# P01_PMIC.net
KiCad netlist of a schematic drawn in Altium Designer
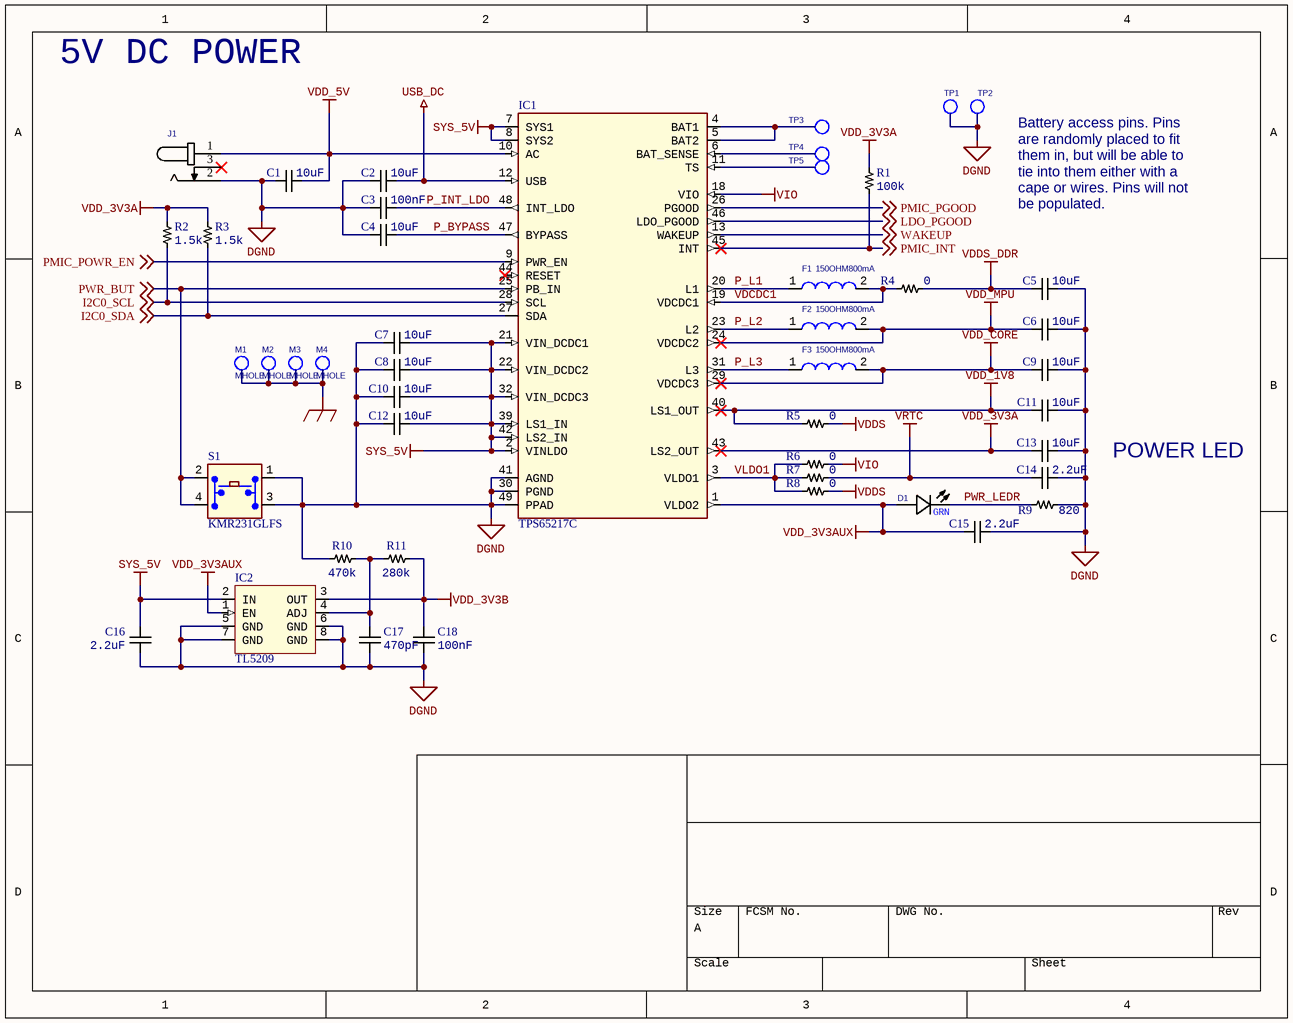
[diagram p0: P01_PMIC.SchDoc]

(export (version "E")
  (design (tool "Eeschema 10.0.6"))
  (components
    (comp (ref "C1")
      (value "C2012X6S1A106K085AC")
      (footprint "Orient:CAP0805")
      (description "MLCC 10uF 0805 SMD")
      (fields
        (field (name "MANUFACTURER") "TDK")
        (field (name "TOLERANCE") "10%")
        (field (name "CAPACITANCE") "10uF")
      )
      (libsource (lib "Orient") (part "CAP_10uF"))
    )
    (comp (ref "C2")
      (value "C2012X6S1A106K085AC")
      (footprint "Orient:CAP0805")
      (description "MLCC 10uF 0805 SMD")
      (fields
        (field (name "MANUFACTURER") "TDK")
        (field (name "TOLERANCE") "10%")
        (field (name "CAPACITANCE") "10uF")
      )
      (libsource (lib "Orient") (part "CAP_10uF"))
    )
    (comp (ref "C3")
      (value "C0402C104K4RACTU")
      (footprint "Orient:CAP0402")
      (description "MLCC 100nF 0402 SMD")
      (fields
        (field (name "MANUFACTURER") "KEMET")
        (field (name "TOLERANCE") "10%")
        (field (name "CAPACITANCE") "100nF")
      )
      (libsource (lib "Orient") (part "CAP_100nF"))
    )
    (comp (ref "C4")
      (value "C2012X6S1A106K085AC")
      (footprint "Orient:CAP0805")
      (description "MLCC 10uF 0805 SMD")
      (fields
        (field (name "MANUFACTURER") "TDK")
        (field (name "TOLERANCE") "10%")
        (field (name "CAPACITANCE") "10uF")
      )
      (libsource (lib "Orient") (part "CAP_10uF"))
    )
    (comp (ref "C5")
      (value "C2012X6S1A106K085AC")
      (footprint "Orient:CAP0805")
      (description "MLCC 10uF 0805 SMD")
      (fields
        (field (name "MANUFACTURER") "TDK")
        (field (name "TOLERANCE") "10%")
        (field (name "CAPACITANCE") "10uF")
      )
      (libsource (lib "Orient") (part "CAP_10uF"))
    )
    (comp (ref "C6")
      (value "C2012X6S1A106K085AC")
      (footprint "Orient:CAP0805")
      (description "MLCC 10uF 0805 SMD")
      (fields
        (field (name "MANUFACTURER") "TDK")
        (field (name "TOLERANCE") "10%")
        (field (name "CAPACITANCE") "10uF")
      )
      (libsource (lib "Orient") (part "CAP_10uF"))
    )
    (comp (ref "C7")
      (value "C2012X6S1A106K085AC")
      (footprint "Orient:CAP0805")
      (description "MLCC 10uF 0805 SMD")
      (fields
        (field (name "MANUFACTURER") "TDK")
        (field (name "TOLERANCE") "10%")
        (field (name "CAPACITANCE") "10uF")
      )
      (libsource (lib "Orient") (part "CAP_10uF"))
    )
    (comp (ref "C8")
      (value "C2012X6S1A106K085AC")
      (footprint "Orient:CAP0805")
      (description "MLCC 10uF 0805 SMD")
      (fields
        (field (name "MANUFACTURER") "TDK")
        (field (name "TOLERANCE") "10%")
        (field (name "CAPACITANCE") "10uF")
      )
      (libsource (lib "Orient") (part "CAP_10uF"))
    )
    (comp (ref "C9")
      (value "C2012X6S1A106K085AC")
      (footprint "Orient:CAP0805")
      (description "MLCC 10uF 0805 SMD")
      (fields
        (field (name "MANUFACTURER") "TDK")
        (field (name "TOLERANCE") "10%")
        (field (name "CAPACITANCE") "10uF")
      )
      (libsource (lib "Orient") (part "CAP_10uF"))
    )
    (comp (ref "C10")
      (value "C2012X6S1A106K085AC")
      (footprint "Orient:CAP0805")
      (description "MLCC 10uF 0805 SMD")
      (fields
        (field (name "MANUFACTURER") "TDK")
        (field (name "TOLERANCE") "10%")
        (field (name "CAPACITANCE") "10uF")
      )
      (libsource (lib "Orient") (part "CAP_10uF"))
    )
    (comp (ref "C11")
      (value "C2012X6S1A106K085AC")
      (footprint "Orient:CAP0805")
      (description "MLCC 10uF 0805 SMD")
      (fields
        (field (name "MANUFACTURER") "TDK")
        (field (name "TOLERANCE") "10%")
        (field (name "CAPACITANCE") "10uF")
      )
      (libsource (lib "Orient") (part "CAP_10uF"))
    )
    (comp (ref "C12")
      (value "C2012X6S1A106K085AC")
      (footprint "Orient:CAP0805")
      (description "MLCC 10uF 0805 SMD")
      (fields
        (field (name "MANUFACTURER") "TDK")
        (field (name "TOLERANCE") "10%")
        (field (name "CAPACITANCE") "10uF")
      )
      (libsource (lib "Orient") (part "CAP_10uF"))
    )
    (comp (ref "C13")
      (value "C2012X6S1A106K085AC")
      (footprint "Orient:CAP0805")
      (description "MLCC 10uF 0805 SMD")
      (fields
        (field (name "MANUFACTURER") "TDK")
        (field (name "TOLERANCE") "10%")
        (field (name "CAPACITANCE") "10uF")
      )
      (libsource (lib "Orient") (part "CAP_10uF"))
    )
    (comp (ref "C14")
      (value "C1005X5R0J225K050BC")
      (footprint "Orient:CAP0402")
      (description "MLCC 2.2uF 0402 SMD")
      (fields
        (field (name "MANUFACTURER") "TDK")
        (field (name "TOLERANCE") "10%")
        (field (name "CAPACITANCE") "2.2uF")
      )
      (libsource (lib "Orient") (part "CAP_2.2uF"))
    )
    (comp (ref "C15")
      (value "C1005X5R0J225K050BC")
      (footprint "Orient:CAP0402")
      (description "MLCC 2.2uF 0402 SMD")
      (fields
        (field (name "MANUFACTURER") "TDK")
        (field (name "TOLERANCE") "10%")
        (field (name "CAPACITANCE") "2.2uF")
      )
      (libsource (lib "Orient") (part "CAP_2.2uF"))
    )
    (comp (ref "C16")
      (value "C1005X5R0J225K050BC")
      (footprint "Orient:CAP0402")
      (description "MLCC 2.2uF 0402 SMD")
      (fields
        (field (name "MANUFACTURER") "TDK")
        (field (name "TOLERANCE") "10%")
        (field (name "CAPACITANCE") "2.2uF")
      )
      (libsource (lib "Orient") (part "CAP_2.2uF"))
    )
    (comp (ref "C17")
      (value "GRM155R71H471KA01D")
      (footprint "Orient:CAP0402")
      (description "MLCC 470pF 0402 SMD")
      (fields
        (field (name "MANUFACTURER") "Murata")
        (field (name "TOLERANCE") "10%")
        (field (name "CAPACITANCE") "470pF")
      )
      (libsource (lib "Orient") (part "CAP_470pF"))
    )
    (comp (ref "C18")
      (value "C0402C104K4RACTU")
      (footprint "Orient:CAP0402")
      (description "MLCC 100nF 0402 SMD")
      (fields
        (field (name "MANUFACTURER") "KEMET")
        (field (name "TOLERANCE") "10%")
        (field (name "CAPACITANCE") "100nF")
      )
      (libsource (lib "Orient") (part "CAP_100nF"))
    )
    (comp (ref "D1")
      (value "598-8170-107F")
      (footprint "Orient:LED_0603")
      (description "LED GREEN CLEAR 0805 SMD")
      (fields
        (field (name "MANUFACTURER") "Lite-On Inc")
        (field (name "MANUFACTURER PART NUMBER") "LTST-C170KGKT")
      )
      (libsource (lib "Orient") (part "LED_LTST-C150GKT"))
    )
    (comp (ref "F1")
      (value "150OHM800mA")
      (footprint "Orient:FB0805")
      (description "FERRITE 800MA 150 OHM 0805 SMD")
      (fields
        (field (name "MANUFACTURER") "Laird-Signal Integrity Products")
        (field (name "MANUFACTURER PART NUMBER") "LI0805H151R-10")
      )
      (libsource (lib "Orient") (part "IND"))
    )
    (comp (ref "F2")
      (value "150OHM800mA")
      (footprint "Orient:FB0805")
      (description "FERRITE 800MA 150 OHM 0805 SMD")
      (fields
        (field (name "MANUFACTURER") "Laird-Signal Integrity Products")
        (field (name "MANUFACTURER PART NUMBER") "LI0805H151R-10")
      )
      (libsource (lib "Orient") (part "IND"))
    )
    (comp (ref "F3")
      (value "150OHM800mA")
      (footprint "Orient:FB0805")
      (description "FERRITE 800MA 150 OHM 0805 SMD")
      (fields
        (field (name "MANUFACTURER") "Laird-Signal Integrity Products")
        (field (name "MANUFACTURER PART NUMBER") "LI0805H151R-10")
      )
      (libsource (lib "Orient") (part "IND"))
    )
    (comp (ref "IC1")
      (value "TPS65217C")
      (footprint "Orient:PVQFN-48")
      (description "IC PMIC BATT PWR SYST 48VQFN")
      (fields
        (field (name "MANUFACTURER") "Texas Instruments")
        (field (name "MANUFACTURER PART NUMBER") "TPS65217CRSLR")
      )
      (libsource (lib "Orient") (part "TPS65217C"))
    )
    (comp (ref "IC2")
      (value "TL5209")
      (footprint "Orient:SOIC-8")
      (description "LDO Voltage Regulator")
      (fields
        (field (name "MANUFACTURER") "Texas Instruments")
        (field (name "MANUFACTURER PART NUMBER") "TL5209DR")
      )
      (libsource (lib "Orient") (part "TL5209"))
    )
    (comp (ref "J1")
      (value "PJ-200A")
      (description "CONN PWR JACK 2.1X5.5MM HIGH CUR")
      (fields (field (name "MANUFACTURER") "CUI Inc") (field (name "MANUFACTURER PART NUMBER") "PJ-002AH"))
      (libsource (lib "Orient") (part "Power_Jack"))
    )
    (comp (ref "M1")
      (value "MHOLE")
      (footprint "Orient:MTGH200C125D_PL")
      (libsource (lib "Orient") (part "MHOLE"))
    )
    (comp (ref "M2")
      (value "MHOLE")
      (footprint "Orient:MTGH200C125D_PL")
      (libsource (lib "Orient") (part "MHOLE"))
    )
    (comp (ref "M3")
      (value "MHOLE")
      (footprint "Orient:MTGH200C125D_PL")
      (libsource (lib "Orient") (part "MHOLE"))
    )
    (comp (ref "M4")
      (value "MHOLE")
      (footprint "Orient:MTGH200C125D_PL")
      (libsource (lib "Orient") (part "MHOLE"))
    )
    (comp (ref "R1")
      (value "RC0402FR-07100KL")
      (footprint "Orient:RES0402")
      (description "Resistor 100kOhm 0402 SMD")
      (fields
        (field (name "MANUFACTURER") "Yageo")
        (field (name "TOLERANCE") "1%")
        (field (name "RESISTANCE") "100k")
      )
      (libsource (lib "Orient") (part "RES_100k"))
    )
    (comp (ref "R2")
      (value "RC0402FR-071K5L")
      (footprint "Orient:RES0402")
      (description "Resistor 1.5kOhm 0402 SMD")
      (fields
        (field (name "MANUFACTURER") "Yageo")
        (field (name "TOLERANCE") "1%")
        (field (name "RESISTANCE") "1.5k")
      )
      (libsource (lib "Orient") (part "RES_1.5k"))
    )
    (comp (ref "R3")
      (value "RC0402FR-071K5L")
      (footprint "Orient:RES0402")
      (description "Resistor 1.5kOhm 0402 SMD")
      (fields
        (field (name "MANUFACTURER") "Yageo")
        (field (name "TOLERANCE") "1%")
        (field (name "RESISTANCE") "1.5k")
      )
      (libsource (lib "Orient") (part "RES_1.5k"))
    )
    (comp (ref "R4")
      (value "RC0402JR-070RL")
      (footprint "Orient:RES0402")
      (description "Resistor 0Ohm 0402 SMD")
      (fields
        (field (name "MANUFACTURER") "Yageo")
        (field (name "TOLERANCE") "5%")
        (field (name "RESISTANCE") "0")
      )
      (libsource (lib "Orient") (part "RES_0"))
    )
    (comp (ref "R5")
      (value "RC0402JR-070RL")
      (footprint "Orient:RES0402")
      (description "Resistor 0Ohm 0402 SMD")
      (fields
        (field (name "MANUFACTURER") "Yageo")
        (field (name "TOLERANCE") "5%")
        (field (name "RESISTANCE") "0")
      )
      (libsource (lib "Orient") (part "RES_0"))
    )
    (comp (ref "R6")
      (value "RC0402JR-070RL")
      (footprint "Orient:RES0402")
      (description "Resistor 0Ohm 0402 SMD")
      (fields
        (field (name "MANUFACTURER") "Yageo")
        (field (name "TOLERANCE") "5%")
        (field (name "RESISTANCE") "0")
      )
      (libsource (lib "Orient") (part "RES_0"))
    )
    (comp (ref "R7")
      (value "RC0402JR-070RL")
      (footprint "Orient:RES0402")
      (description "Resistor 0Ohm 0402 SMD")
      (fields
        (field (name "MANUFACTURER") "Yageo")
        (field (name "TOLERANCE") "5%")
        (field (name "RESISTANCE") "0")
      )
      (libsource (lib "Orient") (part "RES_0"))
    )
    (comp (ref "R8")
      (value "RC0402JR-070RL")
      (footprint "Orient:RES0402")
      (description "Resistor 0Ohm 0402 SMD")
      (fields
        (field (name "MANUFACTURER") "Yageo")
        (field (name "TOLERANCE") "5%")
        (field (name "RESISTANCE") "0")
      )
      (libsource (lib "Orient") (part "RES_0"))
    )
    (comp (ref "R9")
      (value "RC0402FR-07820RL")
      (footprint "Orient:RES0402")
      (description "Resistor 820Ohm 0402 SMD")
      (fields
        (field (name "MANUFACTURER") "Yageo")
        (field (name "TOLERANCE") "1%")
        (field (name "RESISTANCE") "820")
      )
      (libsource (lib "Orient") (part "RES_820"))
    )
    (comp (ref "R10")
      (value "RC0402FR-07470KL")
      (footprint "Orient:RES0402")
      (description "Resistor 470kOhm 0402 SMD")
      (fields
        (field (name "MANUFACTURER") "Yageo")
        (field (name "TOLERANCE") "1%")
        (field (name "RESISTANCE") "470k")
      )
      (libsource (lib "Orient") (part "RES_470k"))
    )
    (comp (ref "R11")
      (value "RC0402FR-07280KL")
      (footprint "Orient:RES0402")
      (description "Resistor 280kOhm 0402 SMD")
      (fields
        (field (name "MANUFACTURER") "Yageo")
        (field (name "TOLERANCE") "1%")
        (field (name "RESISTANCE") "280k")
      )
      (libsource (lib "Orient") (part "RES_280k"))
    )
    (comp (ref "S1")
      (value "KMR231GLFS")
      (footprint "Orient:SW4SMD_63X161LS")
      (description "Microminiature Tact Switch for SMT")
      (fields (field (name "MANUFACTURER") "C&K Components"))
      (libsource (lib "Orient") (part "KMR2"))
    )
    (comp (ref "TP1")
      (value "TESTPT1")
      (footprint "Orient:tp1-8040")
      (libsource (lib "Orient") (part "TESTPT1"))
    )
    (comp (ref "TP2")
      (value "TESTPT1")
      (footprint "Orient:tp1-8040")
      (libsource (lib "Orient") (part "TESTPT1"))
    )
    (comp (ref "TP3")
      (value "TESTPT1")
      (footprint "Orient:tp1-8040")
      (libsource (lib "Orient") (part "TESTPT1"))
    )
    (comp (ref "TP4")
      (value "TESTPT1")
      (footprint "Orient:tp1-8040")
      (libsource (lib "Orient") (part "TESTPT1"))
    )
    (comp (ref "TP5")
      (value "TESTPT1")
      (footprint "Orient:tp1-8040")
      (libsource (lib "Orient") (part "TESTPT1"))
    )
  )
  (nets
    (net (code "1") (name "/PWR_LEDR") (class "Default")
      (node (ref "D1") (pin "1") (pinfunction "C_1") (pintype "passive"))
      (node (ref "R9") (pin "1") (pintype "passive"))
    )
    (net (code "2") (name "/P_BYPASS") (class "Default")
      (node (ref "C4") (pin "1") (pintype "passive"))
      (node (ref "IC1") (pin "47") (pinfunction "BYPASS_47") (pintype "output"))
    )
    (net (code "3") (name "/P_INT_LDO") (class "Default")
      (node (ref "C3") (pin "1") (pintype "passive"))
      (node (ref "IC1") (pin "48") (pinfunction "INT_LDO_48") (pintype "output"))
    )
    (net (code "4") (name "/P_L1") (class "Default")
      (node (ref "F1") (pin "1") (pinfunction "1_1") (pintype "passive"))
      (node (ref "IC1") (pin "20") (pinfunction "L1_20") (pintype "output"))
    )
    (net (code "5") (name "/P_L2") (class "Default")
      (node (ref "F2") (pin "1") (pinfunction "1_1") (pintype "passive"))
      (node (ref "IC1") (pin "23") (pinfunction "L2_23") (pintype "output"))
    )
    (net (code "6") (name "/P_L3") (class "Default")
      (node (ref "F3") (pin "1") (pinfunction "1_1") (pintype "passive"))
      (node (ref "IC1") (pin "31") (pinfunction "L3_31") (pintype "output"))
    )
    (net (code "7") (name "/VDCDC1") (class "Default")
      (node (ref "F1") (pin "2") (pinfunction "2_2") (pintype "passive"))
      (node (ref "IC1") (pin "19") (pinfunction "VDCDC1_19") (pintype "input"))
      (node (ref "R4") (pin "1") (pintype "passive"))
    )
    (net (code "8") (name "/VLDO1") (class "Default")
      (node (ref "IC1") (pin "3") (pinfunction "VLDO1_3") (pintype "output"))
      (node (ref "R6") (pin "1") (pintype "passive"))
      (node (ref "R7") (pin "1") (pintype "passive"))
      (node (ref "R8") (pin "1") (pintype "passive"))
    )
    (net (code "9") (name "DGND") (class "Default")
      (node (ref "C1") (pin "2") (pintype "passive"))
      (node (ref "C10") (pin "2") (pintype "passive"))
      (node (ref "C11") (pin "1") (pintype "passive"))
      (node (ref "C12") (pin "2") (pintype "passive"))
      (node (ref "C13") (pin "1") (pintype "passive"))
      (node (ref "C14") (pin "1") (pintype "passive"))
      (node (ref "C15") (pin "1") (pintype "passive"))
      (node (ref "C16") (pin "2") (pintype "passive"))
      (node (ref "C17") (pin "2") (pintype "passive"))
      (node (ref "C18") (pin "2") (pintype "passive"))
      (node (ref "C2") (pin "2") (pintype "passive"))
      (node (ref "C3") (pin "2") (pintype "passive"))
      (node (ref "C4") (pin "2") (pintype "passive"))
      (node (ref "C5") (pin "1") (pintype "passive"))
      (node (ref "C6") (pin "1") (pintype "passive"))
      (node (ref "C7") (pin "2") (pintype "passive"))
      (node (ref "C8") (pin "2") (pintype "passive"))
      (node (ref "C9") (pin "1") (pintype "passive"))
      (node (ref "IC1") (pin "30") (pinfunction "PGND_30") (pintype "power_in"))
      (node (ref "IC1") (pin "41") (pinfunction "AGND_41") (pintype "power_in"))
      (node (ref "IC1") (pin "49") (pinfunction "PPAD_49") (pintype "power_in"))
      (node (ref "IC2") (pin "5") (pinfunction "GND_5") (pintype "power_in"))
      (node (ref "IC2") (pin "6") (pinfunction "GND_6") (pintype "power_in"))
      (node (ref "IC2") (pin "7") (pinfunction "GND_7") (pintype "power_in"))
      (node (ref "IC2") (pin "8") (pinfunction "GND_8") (pintype "power_in"))
      (node (ref "J1") (pin "2") (pinfunction "2_2") (pintype "passive"))
      (node (ref "R10") (pin "1") (pintype "passive"))
      (node (ref "R9") (pin "2") (pintype "passive"))
      (node (ref "S1") (pin "1") (pinfunction "A1_1") (pintype "passive"))
      (node (ref "S1") (pin "3") (pinfunction "A3_3") (pintype "passive"))
      (node (ref "TP1") (pin "1") (pinfunction "TP_1") (pintype "passive"))
      (node (ref "TP2") (pin "1") (pinfunction "TP_1") (pintype "passive"))
    )
    (net (code "10") (name "GND_EARTH") (class "Default")
      (node (ref "M1") (pin "1") (pinfunction "TP_1") (pintype "passive"))
      (node (ref "M2") (pin "1") (pinfunction "TP_1") (pintype "passive"))
      (node (ref "M3") (pin "1") (pinfunction "TP_1") (pintype "passive"))
      (node (ref "M4") (pin "1") (pinfunction "TP_1") (pintype "passive"))
    )
    (net (code "11") (name "I2C0_SCL") (class "Default")
      (node (ref "IC1") (pin "28") (pinfunction "SCL_28") (pintype "input"))
      (node (ref "R2") (pin "1") (pintype "passive"))
    )
    (net (code "12") (name "I2C0_SDA") (class "Default")
      (node (ref "IC1") (pin "27") (pinfunction "SDA_27") (pintype "bidirectional"))
      (node (ref "R3") (pin "1") (pintype "passive"))
    )
    (net (code "13") (name "LDO_PGOOD") (class "Default")
      (node (ref "IC1") (pin "46") (pinfunction "LDO_PGOOD_46") (pintype "output"))
    )
    (net (code "14") (name "Net-(IC1-BAT1)") (class "Default")
      (node (ref "IC1") (pin "4") (pinfunction "BAT1_4") (pintype "bidirectional"))
      (node (ref "IC1") (pin "5") (pinfunction "BAT2_5") (pintype "bidirectional"))
      (node (ref "TP3") (pin "1") (pinfunction "TP_1") (pintype "passive"))
    )
    (net (code "15") (name "Net-(IC1-BAT_SENSE)") (class "Default")
      (node (ref "IC1") (pin "6") (pinfunction "BAT_SENSE_6") (pintype "input"))
      (node (ref "TP4") (pin "1") (pinfunction "TP_1") (pintype "passive"))
    )
    (net (code "16") (name "Net-(IC1-TS)") (class "Default")
      (node (ref "IC1") (pin "11") (pinfunction "TS_11") (pintype "input"))
      (node (ref "TP5") (pin "1") (pinfunction "TP_1") (pintype "passive"))
    )
    (net (code "17") (name "Net-(IC2-ADJ)") (class "Default")
      (node (ref "C17") (pin "1") (pintype "passive"))
      (node (ref "IC2") (pin "4") (pinfunction "ADJ_4") (pintype "passive"))
      (node (ref "R10") (pin "2") (pintype "passive"))
      (node (ref "R11") (pin "1") (pintype "passive"))
    )
    (net (code "18") (name "PMIC_INT") (class "Default")
      (node (ref "IC1") (pin "45") (pinfunction "INT_45") (pintype "output"))
      (node (ref "R1") (pin "1") (pintype "passive"))
    )
    (net (code "19") (name "PMIC_PGOOD") (class "Default")
      (node (ref "IC1") (pin "26") (pinfunction "PGOOD_26") (pintype "output"))
    )
    (net (code "20") (name "PMIC_POWR_EN") (class "Default")
      (node (ref "IC1") (pin "9") (pinfunction "PWR_EN_9") (pintype "input"))
    )
    (net (code "21") (name "PWR_BUT") (class "Default")
      (node (ref "IC1") (pin "25") (pinfunction "PB_IN_25") (pintype "input"))
      (node (ref "S1") (pin "2") (pinfunction "A2_2") (pintype "passive"))
      (node (ref "S1") (pin "4") (pinfunction "4_4") (pintype "power_in"))
    )
    (net (code "22") (name "SYS_5V") (class "Default")
      (node (ref "C10") (pin "1") (pintype "passive"))
      (node (ref "C12") (pin "1") (pintype "passive"))
      (node (ref "C16") (pin "1") (pintype "passive"))
      (node (ref "C7") (pin "1") (pintype "passive"))
      (node (ref "C8") (pin "1") (pintype "passive"))
      (node (ref "IC1") (pin "2") (pinfunction "VINLDO_2") (pintype "input"))
      (node (ref "IC1") (pin "21") (pinfunction "VIN_DCDC1_21") (pintype "input"))
      (node (ref "IC1") (pin "22") (pinfunction "VIN_DCDC2_22") (pintype "input"))
      (node (ref "IC1") (pin "32") (pinfunction "VIN_DCDC3_32") (pintype "input"))
      (node (ref "IC1") (pin "39") (pinfunction "LS1_IN_39") (pintype "input"))
      (node (ref "IC1") (pin "42") (pinfunction "LS2_IN_42") (pintype "input"))
      (node (ref "IC1") (pin "7") (pinfunction "SYS1_7") (pintype "passive"))
      (node (ref "IC1") (pin "8") (pinfunction "SYS2_8") (pintype "passive"))
      (node (ref "IC2") (pin "2") (pinfunction "IN_2") (pintype "power_in"))
    )
    (net (code "23") (name "USB_DC") (class "Default")
      (node (ref "C2") (pin "1") (pintype "passive"))
      (node (ref "IC1") (pin "12") (pinfunction "USB_12") (pintype "input"))
    )
    (net (code "24") (name "VDDS") (class "Default")
      (node (ref "R5") (pin "2") (pintype "passive"))
      (node (ref "R8") (pin "2") (pintype "passive"))
    )
    (net (code "25") (name "VDDS_DDR") (class "Default")
      (node (ref "C5") (pin "2") (pintype "passive"))
      (node (ref "R4") (pin "2") (pintype "passive"))
    )
    (net (code "26") (name "VDD_1V8") (class "Default")
      (node (ref "C11") (pin "2") (pintype "passive"))
      (node (ref "IC1") (pin "40") (pinfunction "LS1_OUT_40") (pintype "output"))
      (node (ref "R5") (pin "1") (pintype "passive"))
    )
    (net (code "27") (name "VDD_3V3A") (class "Default")
      (node (ref "C13") (pin "2") (pintype "passive"))
      (node (ref "IC1") (pin "43") (pinfunction "LS2_OUT_43") (pintype "output"))
      (node (ref "R1") (pin "2") (pintype "passive"))
      (node (ref "R2") (pin "2") (pintype "passive"))
      (node (ref "R3") (pin "2") (pintype "passive"))
    )
    (net (code "28") (name "VDD_3V3AUX") (class "Default")
      (node (ref "C15") (pin "2") (pintype "passive"))
      (node (ref "D1") (pin "2") (pinfunction "A_2") (pintype "passive"))
      (node (ref "IC1") (pin "1") (pinfunction "VLDO2_1") (pintype "output"))
      (node (ref "IC2") (pin "1") (pinfunction "EN_1") (pintype "input"))
    )
    (net (code "29") (name "VDD_3V3B") (class "Default")
      (node (ref "C18") (pin "1") (pintype "passive"))
      (node (ref "IC2") (pin "3") (pinfunction "OUT_3") (pintype "power_in"))
      (node (ref "R11") (pin "2") (pintype "passive"))
    )
    (net (code "30") (name "VDD_5V") (class "Default")
      (node (ref "C1") (pin "1") (pintype "passive"))
      (node (ref "IC1") (pin "10") (pinfunction "AC_10") (pintype "input"))
      (node (ref "J1") (pin "1") (pinfunction "1_1") (pintype "passive"))
    )
    (net (code "31") (name "VDD_CORE") (class "Default")
      (node (ref "C9") (pin "2") (pintype "passive"))
      (node (ref "F3") (pin "2") (pinfunction "2_2") (pintype "passive"))
      (node (ref "IC1") (pin "29") (pinfunction "VDCDC3_29") (pintype "output"))
    )
    (net (code "32") (name "VDD_MPU") (class "Default")
      (node (ref "C6") (pin "2") (pintype "passive"))
      (node (ref "F2") (pin "2") (pinfunction "2_2") (pintype "passive"))
      (node (ref "IC1") (pin "24") (pinfunction "VDCDC2_24") (pintype "output"))
    )
    (net (code "33") (name "VIO") (class "Default")
      (node (ref "IC1") (pin "18") (pinfunction "VIO_18") (pintype "input"))
      (node (ref "R6") (pin "2") (pintype "passive"))
    )
    (net (code "34") (name "VRTC") (class "Default")
      (node (ref "C14") (pin "2") (pintype "passive"))
      (node (ref "R7") (pin "2") (pintype "passive"))
    )
    (net (code "35") (name "WAKEUP") (class "Default")
      (node (ref "IC1") (pin "13") (pinfunction "WAKEUP_13") (pintype "output"))
    )
    (net (code "36") (name "unconnected-(IC1-RESET-Pad44)") (class "Default")
      (node (ref "IC1") (pin "44") (pinfunction "RESET_44") (pintype "input+no_connect"))
    )
    (net (code "37") (name "unconnected-(J1-Pad3)") (class "Default")
      (node (ref "J1") (pin "3") (pinfunction "3_3") (pintype "passive+no_connect"))
    )
  )
)
